# LM74910H_PINOUT.net
KiCad netlist of a schematic drawn in Altium Designer
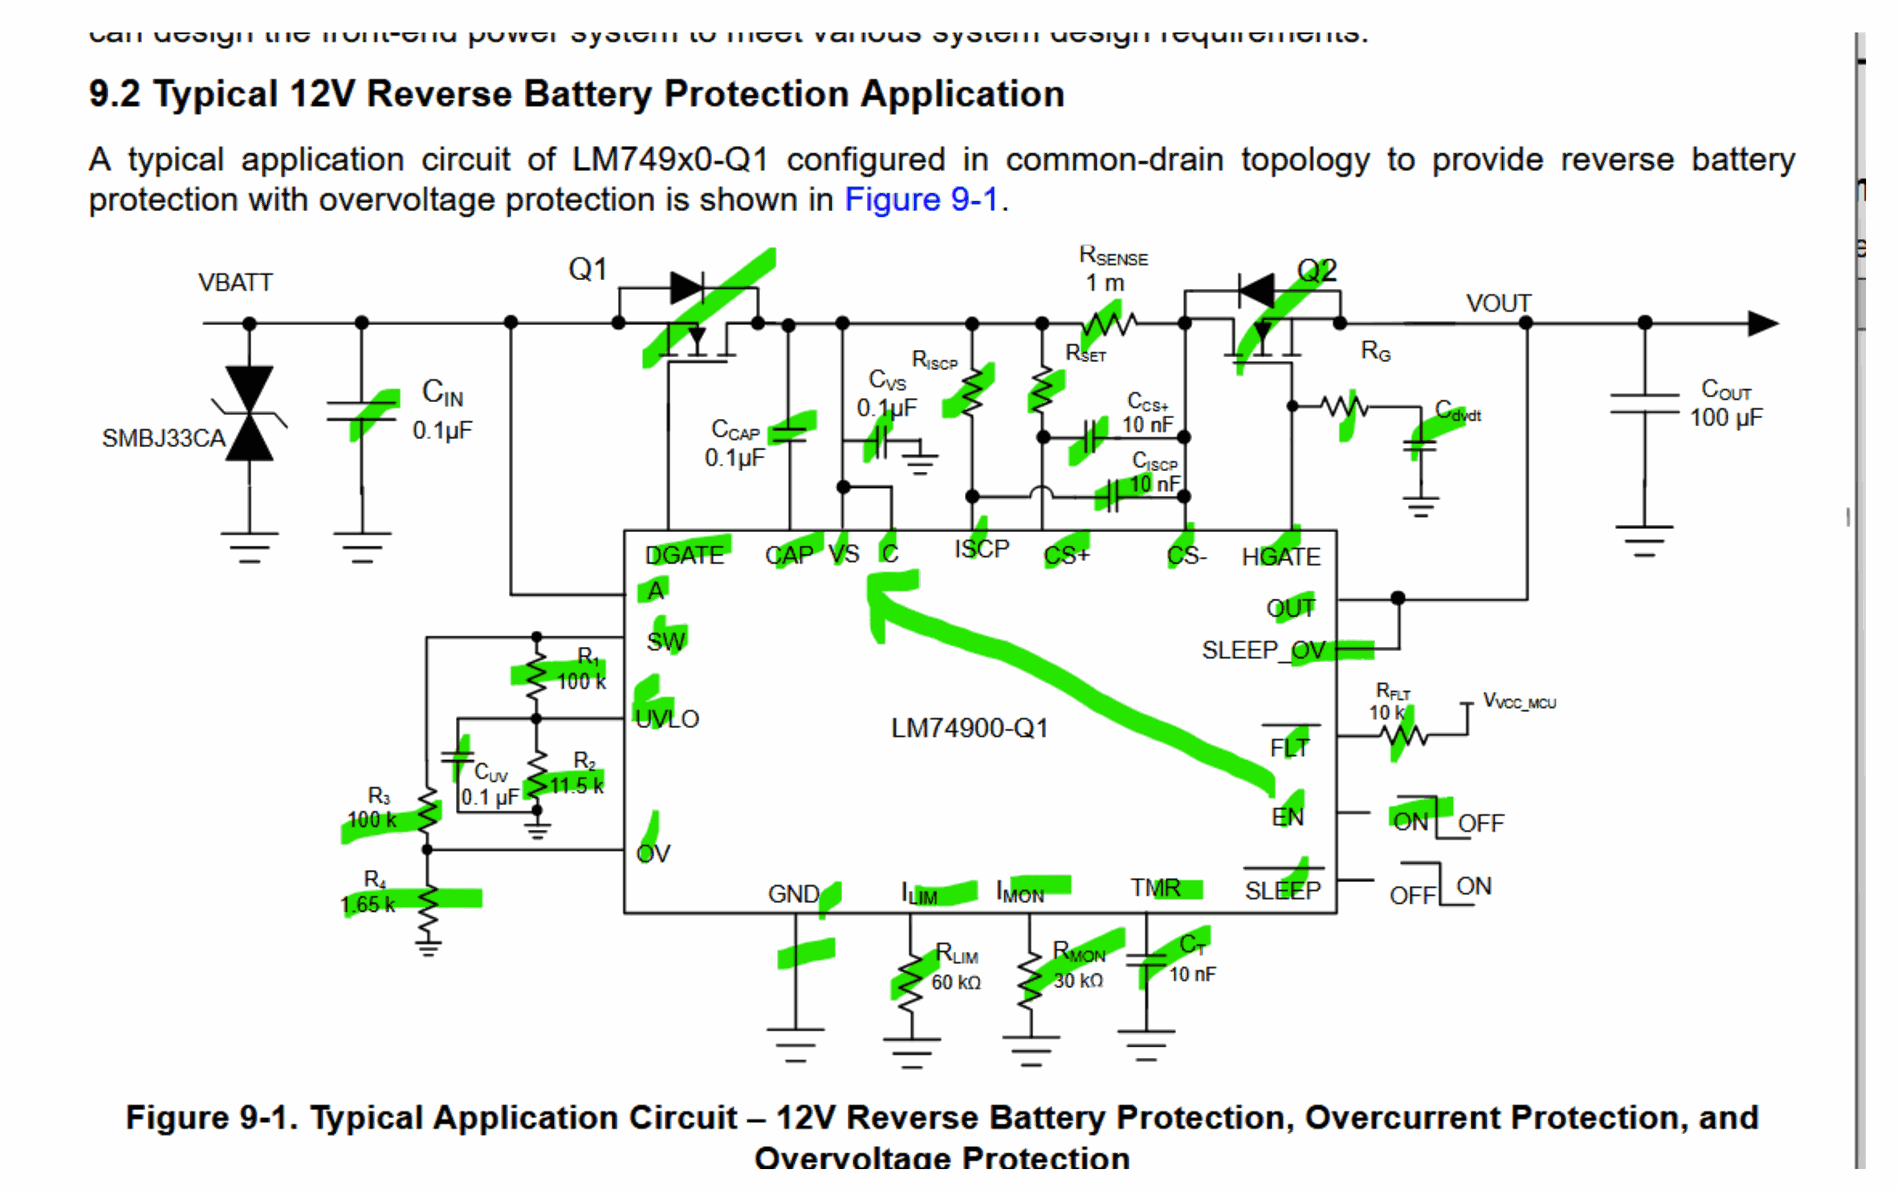
[diagram p0: LM74910H_PINOUT.SchDoc, top]
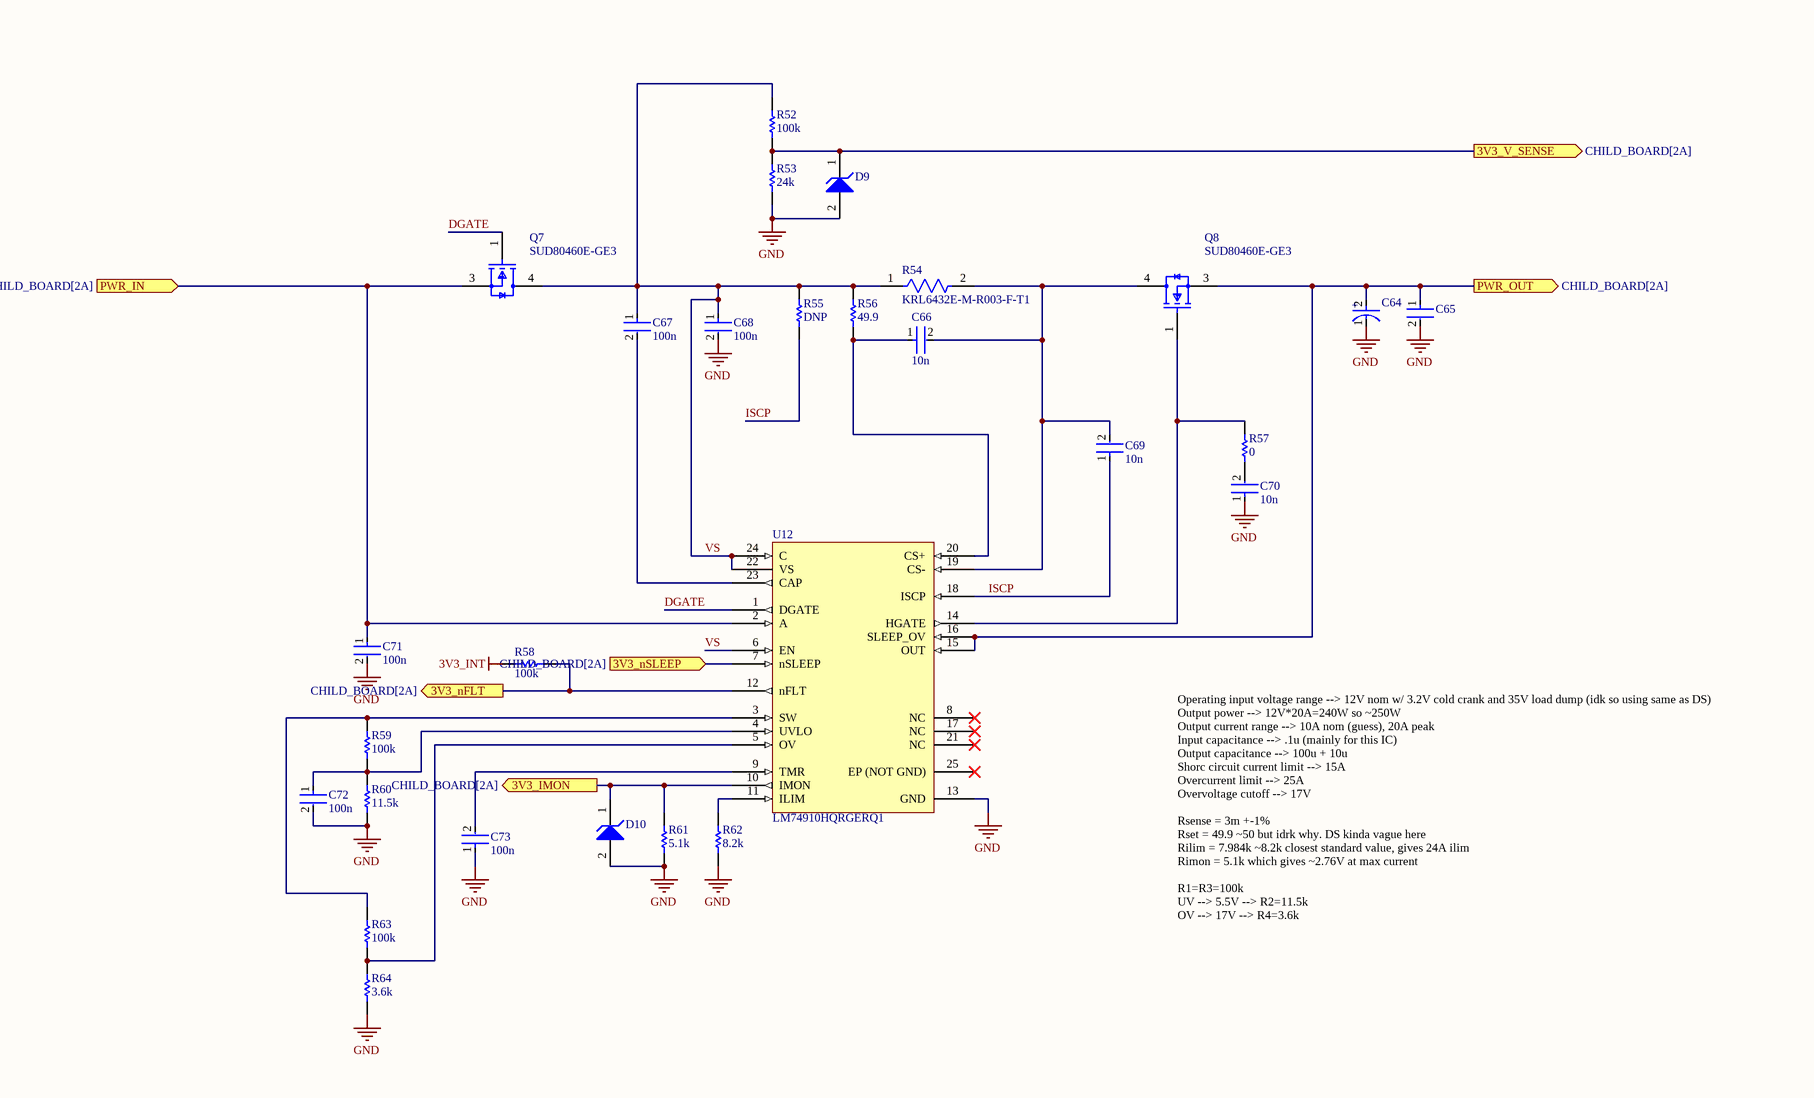
[diagram p1: LM74910H_PINOUT.SchDoc, bottom]

(export (version "E")
  (design (tool "Eeschema 10.0.6"))
  (components
    (comp (ref "C64")
      (value "EEE-FK1H100UR")
      (footprint "FP-FKC-MFG")
      (description "CAP ALUM 10UF 20% 50V SMD")
      (fields (field (name "TOLERANCE") "20%") (field (name "VOLTAGE") "50V"))
      (libsource (lib "Altium Content Vault") (part "a00bbbee19879c290e62620ae7e47b1"))
    )
    (comp (ref "C65")
      (value "12103D106KAT2A")
      (footprint "FP-1210-L_3_3_0_4-W_2_5_0-MFG")
      (description "General Purpose Ceramic Capacitor, 1210, 10uF, 10%, X5R, 15%, 25V")
      (fields (field (name "VOLTAGE") "25V") (field (name "TOLERANCE") "10%"))
      (libsource (lib "Altium Content Vault") (part "b4654b650e69147ec39a6b967a45e02"))
    )
    (comp (ref "C66")
      (value "10n")
      (footprint "FP-0402-L_1_0_0_05-W_0_5-IPC_A")
      (description "LARGE PADS, 0402 CAP, CHANGE COMMENT TO MATCH REAL P/N")
      (libsource (lib "Space Concordia") (part "b4654b650e69147ec39a6b967a45e02"))
    )
    (comp (ref "C67")
      (value "100n")
      (footprint "FP-0402-L_1_0_0_05-W_0_5-IPC_A")
      (description "LARGE PADS, 0402 CAP, CHANGE COMMENT TO MATCH REAL P/N")
      (libsource (lib "Space Concordia") (part "b4654b650e69147ec39a6b967a45e02"))
    )
    (comp (ref "C68")
      (value "100n")
      (footprint "FP-0402-L_1_0_0_05-W_0_5-IPC_A")
      (description "LARGE PADS, 0402 CAP, CHANGE COMMENT TO MATCH REAL P/N")
      (libsource (lib "Space Concordia") (part "b4654b650e69147ec39a6b967a45e02"))
    )
    (comp (ref "C69")
      (value "10n")
      (footprint "FP-0402-L_1_0_0_05-W_0_5-IPC_A")
      (description "LARGE PADS, 0402 CAP, CHANGE COMMENT TO MATCH REAL P/N")
      (libsource (lib "Space Concordia") (part "b4654b650e69147ec39a6b967a45e02"))
    )
    (comp (ref "C70")
      (value "10n")
      (footprint "FP-0402-L_1_0_0_05-W_0_5-IPC_A")
      (description "LARGE PADS, 0402 CAP, CHANGE COMMENT TO MATCH REAL P/N")
      (libsource (lib "Space Concordia") (part "b4654b650e69147ec39a6b967a45e02"))
    )
    (comp (ref "C71")
      (value "100n")
      (footprint "FP-0402-L_1_0_0_05-W_0_5-IPC_A")
      (description "LARGE PADS, 0402 CAP, CHANGE COMMENT TO MATCH REAL P/N")
      (libsource (lib "Space Concordia") (part "b4654b650e69147ec39a6b967a45e02"))
    )
    (comp (ref "C72")
      (value "100n")
      (footprint "FP-0402-L_1_0_0_05-W_0_5-IPC_A")
      (description "LARGE PADS, 0402 CAP, CHANGE COMMENT TO MATCH REAL P/N")
      (libsource (lib "Space Concordia") (part "b4654b650e69147ec39a6b967a45e02"))
    )
    (comp (ref "C73")
      (value "100n")
      (footprint "FP-0402-L_1_0_0_05-W_0_5-IPC_A")
      (description "LARGE PADS, 0402 CAP, CHANGE COMMENT TO MATCH REAL P/N")
      (libsource (lib "Space Concordia") (part "b4654b650e69147ec39a6b967a45e02"))
    )
    (comp (ref "D9")
      (value "DNP/MM5Z3V3T1G")
      (footprint "ONSC-SOD-523-2-502-01_V")
      (description "Zener Voltage Regulator, 500 mW, 2-Pin SOD-523, Pb-Free, Tape and Reel")
      (fields (field (name "MANUFACTURER") "On Semiconductor") (field (name "PARTNUMBER") "MM5Z3V3T1G"))
      (libsource (lib "Altium Content Vault") (part "ONSC-K1A2-2"))
    )
    (comp (ref "D10")
      (value "DNP/MM5Z3V3T1G")
      (footprint "ONSC-SOD-523-2-502-01_V")
      (description "Zener Voltage Regulator, 500 mW, 2-Pin SOD-523, Pb-Free, Tape and Reel")
      (fields (field (name "MANUFACTURER") "On Semiconductor") (field (name "PARTNUMBER") "MM5Z3V3T1G"))
      (libsource (lib "Altium Content Vault") (part "ONSC-K1A2-2"))
    )
    (comp (ref "Q7")
      (value "SUD80460E-GE3")
      (footprint "FP-T16-0236-MFG")
      (description "MOSFET N-CH 150V 42A TO252AA")
      (fields
        (field (name "OCTOPART") "https://octopart.com/sud80460e-ge3-vishay-78440626")
        (field (name "MANUFACTURER") "Vishay")
      )
      (libsource (lib "Altium Content Vault") (part "9dda50919618e2b74f88a68e272f5a4"))
    )
    (comp (ref "Q8")
      (value "SUD80460E-GE3")
      (footprint "FP-T16-0236-MFG")
      (description "MOSFET N-CH 150V 42A TO252AA")
      (fields
        (field (name "OCTOPART") "https://octopart.com/sud80460e-ge3-vishay-78440626")
        (field (name "MANUFACTURER") "Vishay")
      )
      (libsource (lib "Altium Content Vault") (part "9dda50919618e2b74f88a68e272f5a4"))
    )
    (comp (ref "R52")
      (value "100k")
      (footprint "R0603B")
      (description "Resistor")
      (libsource (lib "Space Concordia") (part "Resistor"))
    )
    (comp (ref "R53")
      (value "24k")
      (footprint "R0603B")
      (description "Resistor")
      (libsource (lib "Space Concordia") (part "Resistor"))
    )
    (comp (ref "R54")
      (value "KRL6432E-M-R003-F-T1")
      (footprint "FP-KRL6432E-MFG")
      (description "KRL6432E-M-R003-F-T1 Metal Foil Low Resistance Chip Resistor (long-side terminal), 2512, RoHS")
      (fields (field (name "TOLERANCE") "1%"))
      (libsource (lib "Altium Content Vault") (part "1029c3af85768c4190bb7ad29bc67b5"))
    )
    (comp (ref "R55")
      (value "DNP")
      (footprint "R0603B")
      (description "Resistor")
      (libsource (lib "Space Concordia") (part "Resistor"))
    )
    (comp (ref "R56")
      (value "49.9")
      (footprint "R0603B")
      (description "Resistor")
      (libsource (lib "Space Concordia") (part "Resistor"))
    )
    (comp (ref "R57")
      (value "0")
      (footprint "R0603B")
      (description "Resistor")
      (libsource (lib "Space Concordia") (part "Resistor"))
    )
    (comp (ref "R58")
      (value "100k")
      (footprint "R0603B")
      (description "Resistor")
      (libsource (lib "Space Concordia") (part "Resistor"))
    )
    (comp (ref "R59")
      (value "100k")
      (footprint "R0603B")
      (description "Resistor")
      (libsource (lib "Space Concordia") (part "Resistor"))
    )
    (comp (ref "R60")
      (value "11.5k")
      (footprint "R0603B")
      (description "Resistor")
      (libsource (lib "Space Concordia") (part "Resistor"))
    )
    (comp (ref "R61")
      (value "5.1k")
      (footprint "R0603B")
      (description "Resistor")
      (libsource (lib "Space Concordia") (part "Resistor"))
    )
    (comp (ref "R62")
      (value "8.2k")
      (footprint "R0603B")
      (description "Resistor")
      (libsource (lib "Space Concordia") (part "Resistor"))
    )
    (comp (ref "R63")
      (value "100k")
      (footprint "R0603B")
      (description "Resistor")
      (libsource (lib "Space Concordia") (part "Resistor"))
    )
    (comp (ref "R64")
      (value "3.6k")
      (footprint "R0603B")
      (description "Resistor")
      (libsource (lib "Space Concordia") (part "Resistor"))
    )
    (comp (ref "U12")
      (value "LM74910HQRGERQ1")
      (footprint "QFN50P400X400X100_HS-25N")
      (libsource (lib "Space Concordia") (part "LM74910HQRGERQ1"))
    )
  )
  (nets
    (net (code "1") (name "/3V3_IMON") (class "Default")
      (node (ref "D10") (pin "1") (pinfunction "K_1") (pintype "passive"))
      (node (ref "R61") (pin "2") (pinfunction "2_2") (pintype "passive"))
      (node (ref "U12") (pin "10") (pinfunction "IMON_10") (pintype "output"))
    )
    (net (code "2") (name "/3V3_V_SENSE") (class "Default")
      (node (ref "D9") (pin "1") (pinfunction "K_1") (pintype "passive"))
      (node (ref "R52") (pin "1") (pinfunction "1_1") (pintype "passive"))
      (node (ref "R53") (pin "2") (pinfunction "2_2") (pintype "passive"))
    )
    (net (code "3") (name "/3V3_nFLT") (class "Default")
      (node (ref "R58") (pin "1") (pinfunction "1_1") (pintype "passive"))
      (node (ref "U12") (pin "12") (pinfunction "nFLT_12") (pintype "output"))
    )
    (net (code "4") (name "/3V3_nSLEEP") (class "Default")
      (node (ref "U12") (pin "7") (pinfunction "nSLEEP_7") (pintype "input"))
    )
    (net (code "5") (name "/DGATE") (class "Default")
      (node (ref "Q7") (pin "1") (pinfunction "G_1") (pintype "passive"))
      (node (ref "U12") (pin "1") (pinfunction "DGATE_1") (pintype "output"))
    )
    (net (code "6") (name "/ISCP") (class "Default")
      (node (ref "C69") (pin "1") (pinfunction "1_1") (pintype "passive"))
      (node (ref "R55") (pin "1") (pinfunction "1_1") (pintype "passive"))
      (node (ref "U12") (pin "18") (pinfunction "ISCP_18") (pintype "input"))
    )
    (net (code "7") (name "/PWR_IN") (class "Default")
      (node (ref "C71") (pin "1") (pinfunction "1_1") (pintype "passive"))
      (node (ref "Q7") (pin "3") (pinfunction "S_3") (pintype "passive"))
      (node (ref "U12") (pin "2") (pinfunction "A_2") (pintype "input"))
    )
    (net (code "8") (name "/PWR_OUT") (class "Default")
      (node (ref "C64") (pin "2") (pinfunction "A_2") (pintype "passive"))
      (node (ref "C65") (pin "1") (pinfunction "1_1") (pintype "passive"))
      (node (ref "Q8") (pin "3") (pinfunction "S_3") (pintype "passive"))
      (node (ref "U12") (pin "15") (pinfunction "OUT_15") (pintype "input"))
      (node (ref "U12") (pin "16") (pinfunction "SLEEP_OV_16") (pintype "input"))
    )
    (net (code "9") (name "/VS") (class "Default")
      (node (ref "C67") (pin "1") (pinfunction "1_1") (pintype "passive"))
      (node (ref "C68") (pin "1") (pinfunction "1_1") (pintype "passive"))
      (node (ref "Q7") (pin "4") (pinfunction "D_4") (pintype "passive"))
      (node (ref "R52") (pin "2") (pinfunction "2_2") (pintype "passive"))
      (node (ref "R54") (pin "1") (pinfunction "1_1") (pintype "passive"))
      (node (ref "R55") (pin "2") (pinfunction "2_2") (pintype "passive"))
      (node (ref "R56") (pin "2") (pinfunction "2_2") (pintype "passive"))
      (node (ref "U12") (pin "22") (pinfunction "VS_22") (pintype "power_in"))
      (node (ref "U12") (pin "24") (pinfunction "C_24") (pintype "input"))
      (node (ref "U12") (pin "6") (pinfunction "EN_6") (pintype "input"))
    )
    (net (code "10") (name "3V3_INT") (class "Default")
      (node (ref "R58") (pin "2") (pinfunction "2_2") (pintype "passive"))
    )
    (net (code "11") (name "GND") (class "Default")
      (node (ref "C64") (pin "1") (pinfunction "C_1") (pintype "passive"))
      (node (ref "C65") (pin "2") (pinfunction "2_2") (pintype "passive"))
      (node (ref "C68") (pin "2") (pinfunction "2_2") (pintype "passive"))
      (node (ref "C70") (pin "1") (pinfunction "1_1") (pintype "passive"))
      (node (ref "C71") (pin "2") (pinfunction "2_2") (pintype "passive"))
      (node (ref "C72") (pin "2") (pinfunction "2_2") (pintype "passive"))
      (node (ref "C73") (pin "1") (pinfunction "1_1") (pintype "passive"))
      (node (ref "D10") (pin "2") (pinfunction "A_2") (pintype "passive"))
      (node (ref "D9") (pin "2") (pinfunction "A_2") (pintype "passive"))
      (node (ref "R53") (pin "1") (pinfunction "1_1") (pintype "passive"))
      (node (ref "R60") (pin "1") (pinfunction "1_1") (pintype "passive"))
      (node (ref "R61") (pin "1") (pinfunction "1_1") (pintype "passive"))
      (node (ref "R62") (pin "1") (pinfunction "1_1") (pintype "passive"))
      (node (ref "R64") (pin "1") (pinfunction "1_1") (pintype "passive"))
      (node (ref "U12") (pin "13") (pinfunction "GND_13") (pintype "power_in"))
    )
    (net (code "12") (name "Net-(C70-Pad2)") (class "Default")
      (node (ref "C70") (pin "2") (pinfunction "2_2") (pintype "passive"))
      (node (ref "R57") (pin "1") (pinfunction "1_1") (pintype "passive"))
    )
    (net (code "13") (name "Net-(Q8-D)") (class "Default")
      (node (ref "C66") (pin "2") (pinfunction "2_2") (pintype "passive"))
      (node (ref "C69") (pin "2") (pinfunction "2_2") (pintype "passive"))
      (node (ref "Q8") (pin "4") (pinfunction "D_4") (pintype "passive"))
      (node (ref "R54") (pin "2") (pinfunction "2_2") (pintype "passive"))
      (node (ref "U12") (pin "19") (pinfunction "CS-_19") (pintype "input"))
    )
    (net (code "14") (name "Net-(Q8-G)") (class "Default")
      (node (ref "Q8") (pin "1") (pinfunction "G_1") (pintype "passive"))
      (node (ref "R57") (pin "2") (pinfunction "2_2") (pintype "passive"))
      (node (ref "U12") (pin "14") (pinfunction "HGATE_14") (pintype "output"))
    )
    (net (code "15") (name "Net-(U12-CAP)") (class "Default")
      (node (ref "C67") (pin "2") (pinfunction "2_2") (pintype "passive"))
      (node (ref "U12") (pin "23") (pinfunction "CAP_23") (pintype "output"))
    )
    (net (code "16") (name "Net-(U12-CS+)") (class "Default")
      (node (ref "C66") (pin "1") (pinfunction "1_1") (pintype "passive"))
      (node (ref "R56") (pin "1") (pinfunction "1_1") (pintype "passive"))
      (node (ref "U12") (pin "20") (pinfunction "CS+_20") (pintype "input"))
    )
    (net (code "17") (name "Net-(U12-ILIM)") (class "Default")
      (node (ref "R62") (pin "2") (pinfunction "2_2") (pintype "passive"))
      (node (ref "U12") (pin "11") (pinfunction "ILIM_11") (pintype "input"))
    )
    (net (code "18") (name "Net-(U12-OV)") (class "Default")
      (node (ref "R63") (pin "1") (pinfunction "1_1") (pintype "passive"))
      (node (ref "R64") (pin "2") (pinfunction "2_2") (pintype "passive"))
      (node (ref "U12") (pin "5") (pinfunction "OV_5") (pintype "input"))
    )
    (net (code "19") (name "Net-(U12-SW)") (class "Default")
      (node (ref "R59") (pin "2") (pinfunction "2_2") (pintype "passive"))
      (node (ref "R63") (pin "2") (pinfunction "2_2") (pintype "passive"))
      (node (ref "U12") (pin "3") (pinfunction "SW_3") (pintype "input"))
    )
    (net (code "20") (name "Net-(U12-TMR)") (class "Default")
      (node (ref "C73") (pin "2") (pinfunction "2_2") (pintype "passive"))
      (node (ref "U12") (pin "9") (pinfunction "TMR_9") (pintype "input"))
    )
    (net (code "21") (name "Net-(U12-UVLO)") (class "Default")
      (node (ref "C72") (pin "1") (pinfunction "1_1") (pintype "passive"))
      (node (ref "R59") (pin "1") (pinfunction "1_1") (pintype "passive"))
      (node (ref "R60") (pin "2") (pinfunction "2_2") (pintype "passive"))
      (node (ref "U12") (pin "4") (pinfunction "UVLO_4") (pintype "input"))
    )
    (net (code "22") (name "unconnected-(U12-EP_(NOT_GND)-Pad25)") (class "Default")
      (node (ref "U12") (pin "25") (pinfunction "EP_(NOT_GND)_25") (pintype "passive+no_connect"))
    )
    (net (code "23") (name "unconnected-(U12-NC-Pad8)") (class "Default")
      (node (ref "U12") (pin "8") (pinfunction "NC_8") (pintype "passive+no_connect"))
    )
    (net (code "24") (name "unconnected-(U12-NC-Pad17)") (class "Default")
      (node (ref "U12") (pin "17") (pinfunction "NC_17") (pintype "passive+no_connect"))
    )
    (net (code "25") (name "unconnected-(U12-NC-Pad21)") (class "Default")
      (node (ref "U12") (pin "21") (pinfunction "NC_21") (pintype "passive+no_connect"))
    )
  )
)
